# main.net
KiCad netlist of a schematic drawn in EAGLE
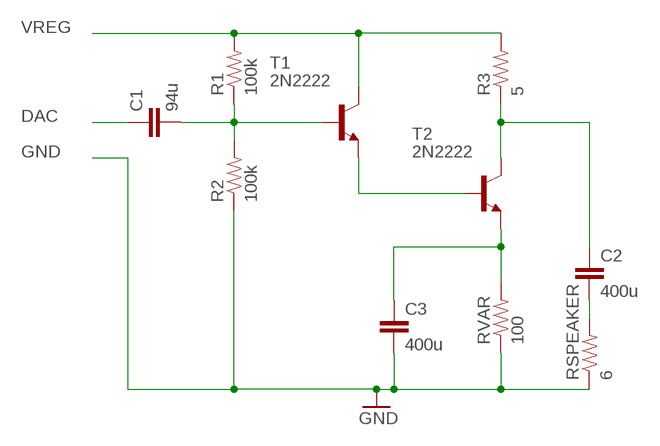
[diagram p0: schematic, sheet 1]

(export (version "E")
  (design (tool "Eeschema 10.0.6"))
  (components
    (comp (ref "C1")
      (value "94u")
      (footprint "eagle-import:CAP-PTH-SMALL-KIT")
      (libsource (lib "eagle-import") (part "CAPKIT"))
    )
    (comp (ref "C2")
      (value "400u")
      (footprint "eagle-import:CAP-PTH-SMALL-KIT")
      (libsource (lib "eagle-import") (part "CAPKIT"))
    )
    (comp (ref "C3")
      (value "400u")
      (footprint "eagle-import:CAP-PTH-SMALL-KIT")
      (libsource (lib "eagle-import") (part "CAPKIT"))
    )
    (comp (ref "R1")
      (value "100k")
      (footprint "eagle-import:AXIAL-0.4")
      (libsource (lib "eagle-import") (part "RESISTORPTH-1/4W"))
    )
    (comp (ref "R2")
      (value "100k")
      (footprint "eagle-import:AXIAL-0.4")
      (libsource (lib "eagle-import") (part "RESISTORPTH-1/4W"))
    )
    (comp (ref "R3")
      (value "5")
      (footprint "eagle-import:AXIAL-0.4")
      (libsource (lib "eagle-import") (part "RESISTORPTH-1/4W"))
    )
    (comp (ref "RSPEAKER")
      (value "6")
      (footprint "eagle-import:AXIAL-0.4")
      (libsource (lib "eagle-import") (part "RESISTORPTH-1/4W"))
    )
    (comp (ref "RVAR")
      (value "100")
      (footprint "eagle-import:AXIAL-0.4")
      (libsource (lib "eagle-import") (part "RESISTORPTH-1/4W"))
    )
    (comp (ref "T1")
      (value "2N2222")
      (footprint "eagle-import:TO18")
      (libsource (lib "eagle-import") (part "2N2222"))
    )
    (comp (ref "T2")
      (value "2N2222")
      (footprint "eagle-import:TO18")
      (libsource (lib "eagle-import") (part "2N2222"))
    )
  )
  (nets
    (net (code "1") (name "/DAC") (class "Default")
      (node (ref "C1") (pin "1") (pinfunction "1_1") (pintype "passive"))
    )
    (net (code "2") (name "/VREG") (class "Default")
      (node (ref "R1") (pin "P$2") (pinfunction "2_P$2") (pintype "passive"))
      (node (ref "R3") (pin "P$2") (pinfunction "2_P$2") (pintype "passive"))
      (node (ref "T1") (pin "3") (pinfunction "C_3") (pintype "passive"))
    )
    (net (code "3") (name "GND") (class "Default")
      (node (ref "C3") (pin "2") (pinfunction "2_2") (pintype "passive"))
      (node (ref "R2") (pin "P$1") (pinfunction "1_P$1") (pintype "passive"))
      (node (ref "RSPEAKER") (pin "P$1") (pinfunction "1_P$1") (pintype "passive"))
      (node (ref "RVAR") (pin "P$1") (pinfunction "1_P$1") (pintype "passive"))
    )
    (net (code "4") (name "Net-(R1-1)") (class "Default")
      (node (ref "C1") (pin "2") (pinfunction "2_2") (pintype "passive"))
      (node (ref "R1") (pin "P$1") (pinfunction "1_P$1") (pintype "passive"))
      (node (ref "R2") (pin "P$2") (pinfunction "2_P$2") (pintype "passive"))
      (node (ref "T1") (pin "2") (pinfunction "B_2") (pintype "passive"))
    )
    (net (code "5") (name "Net-(R3-1)") (class "Default")
      (node (ref "C2") (pin "1") (pinfunction "1_1") (pintype "passive"))
      (node (ref "R3") (pin "P$1") (pinfunction "1_P$1") (pintype "passive"))
      (node (ref "T2") (pin "3") (pinfunction "C_3") (pintype "passive"))
    )
    (net (code "6") (name "Net-(RSPEAKER-2)") (class "Default")
      (node (ref "C2") (pin "2") (pinfunction "2_2") (pintype "passive"))
      (node (ref "RSPEAKER") (pin "P$2") (pinfunction "2_P$2") (pintype "passive"))
    )
    (net (code "7") (name "Net-(RVAR-2)") (class "Default")
      (node (ref "C3") (pin "1") (pinfunction "1_1") (pintype "passive"))
      (node (ref "RVAR") (pin "P$2") (pinfunction "2_P$2") (pintype "passive"))
      (node (ref "T2") (pin "1") (pinfunction "E_1") (pintype "passive"))
    )
    (net (code "8") (name "Net-(T1-E)") (class "Default")
      (node (ref "T1") (pin "1") (pinfunction "E_1") (pintype "passive"))
      (node (ref "T2") (pin "2") (pinfunction "B_2") (pintype "passive"))
    )
  )
)
